# weather_station.net
KiCad netlist of a schematic drawn in EAGLE
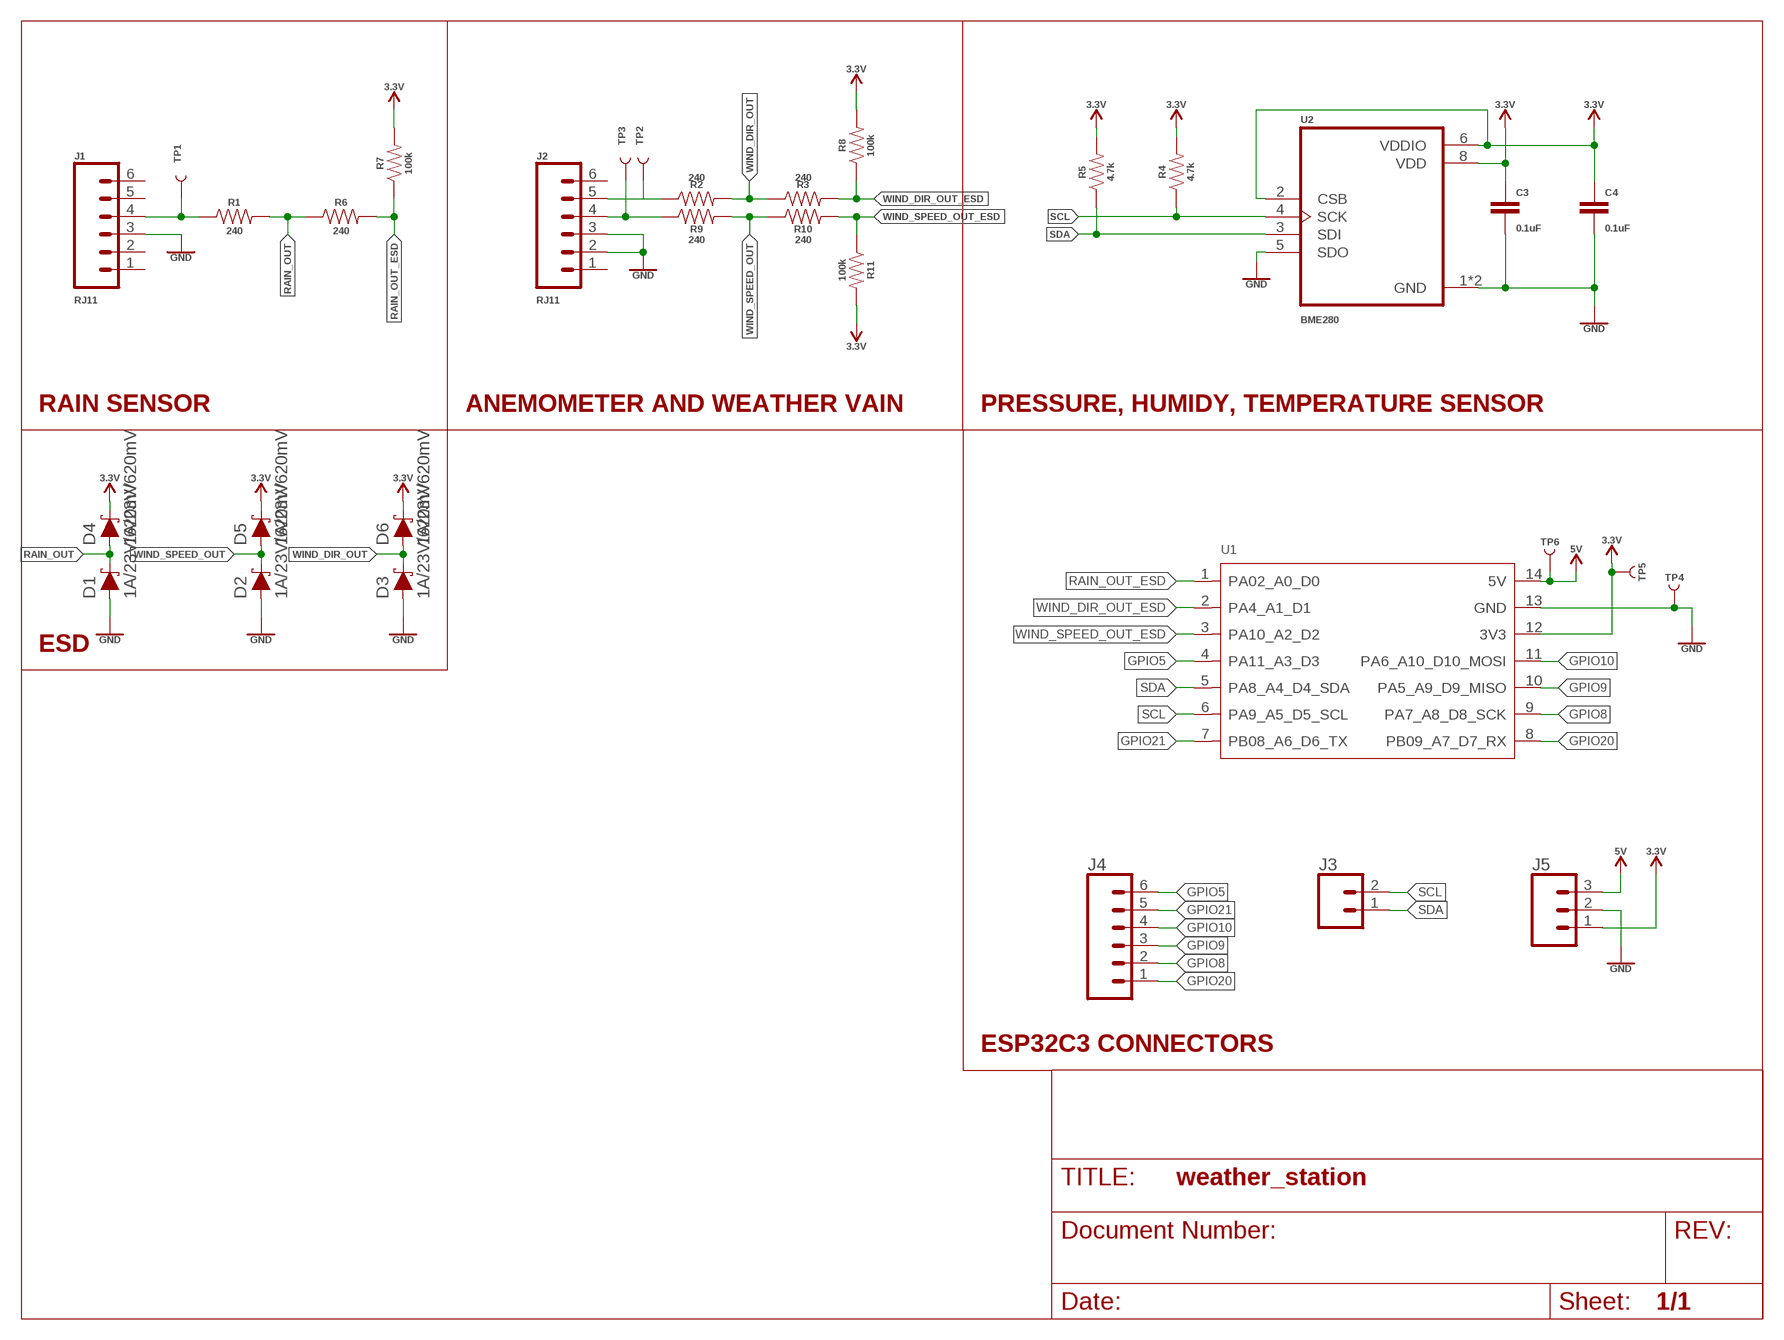
[diagram p0: schematic, sheet 1]

(export (version "E")
  (design (tool "Eeschema 10.0.6"))
  (components
    (comp (ref "C3")
      (value "0.1uF")
      (footprint "eagle-import:0603")
      (libsource (lib "eagle-import") (part "0.1UF-0603-25V-(+80/-20%)"))
    )
    (comp (ref "C4")
      (value "0.1uF")
      (footprint "eagle-import:0603")
      (libsource (lib "eagle-import") (part "0.1UF-0603-25V-(+80/-20%)"))
    )
    (comp (ref "D1")
      (value "1A/23V/620mV")
      (footprint "eagle-import:SOD-323")
      (libsource (lib "eagle-import") (part "DIODE-SCHOTTKY-BAT20J"))
    )
    (comp (ref "D2")
      (value "1A/23V/620mV")
      (footprint "eagle-import:SOD-323")
      (libsource (lib "eagle-import") (part "DIODE-SCHOTTKY-BAT20J"))
    )
    (comp (ref "D3")
      (value "1A/23V/620mV")
      (footprint "eagle-import:SOD-323")
      (libsource (lib "eagle-import") (part "DIODE-SCHOTTKY-BAT20J"))
    )
    (comp (ref "D4")
      (value "1A/23V/620mV")
      (footprint "eagle-import:SOD-323")
      (libsource (lib "eagle-import") (part "DIODE-SCHOTTKY-BAT20J"))
    )
    (comp (ref "D5")
      (value "1A/23V/620mV")
      (footprint "eagle-import:SOD-323")
      (libsource (lib "eagle-import") (part "DIODE-SCHOTTKY-BAT20J"))
    )
    (comp (ref "D6")
      (value "1A/23V/620mV")
      (footprint "eagle-import:SOD-323")
      (libsource (lib "eagle-import") (part "DIODE-SCHOTTKY-BAT20J"))
    )
    (comp (ref "J1")
      (value "RJ11")
      (footprint "eagle-import:RJ11-6")
      (libsource (lib "eagle-import") (part "RJ11-6"))
    )
    (comp (ref "J2")
      (value "RJ11")
      (footprint "eagle-import:RJ11-6")
      (libsource (lib "eagle-import") (part "RJ11-6"))
    )
    (comp (ref "J3")
      (value "CONN_02")
      (footprint "eagle-import:1X02")
      (libsource (lib "eagle-import") (part "CONN_02"))
    )
    (comp (ref "J4")
      (value "CONN_06SILK_FEMALE_PTH")
      (footprint "eagle-import:1X06")
      (libsource (lib "eagle-import") (part "CONN_06SILK_FEMALE_PTH"))
    )
    (comp (ref "J5")
      (value "CONN_03")
      (footprint "eagle-import:1X03")
      (libsource (lib "eagle-import") (part "CONN_03"))
    )
    (comp (ref "R1")
      (value "240")
      (footprint "eagle-import:0603")
      (libsource (lib "eagle-import") (part "240OHM-0603-1/10W-1%"))
    )
    (comp (ref "R2")
      (value "240")
      (footprint "eagle-import:0603")
      (libsource (lib "eagle-import") (part "240OHM-0603-1/10W-1%"))
    )
    (comp (ref "R3")
      (value "240")
      (footprint "eagle-import:0603")
      (libsource (lib "eagle-import") (part "240OHM-0603-1/10W-1%"))
    )
    (comp (ref "R4")
      (value "4.7k")
      (footprint "eagle-import:0603")
      (libsource (lib "eagle-import") (part "4.7KOHM-0603-1/10W-1%"))
    )
    (comp (ref "R5")
      (value "4.7k")
      (footprint "eagle-import:0603")
      (libsource (lib "eagle-import") (part "4.7KOHM-0603-1/10W-1%"))
    )
    (comp (ref "R6")
      (value "240")
      (footprint "eagle-import:0603")
      (libsource (lib "eagle-import") (part "240OHM-0603-1/10W-1%"))
    )
    (comp (ref "R7")
      (value "100k")
      (footprint "eagle-import:0603")
      (libsource (lib "eagle-import") (part "100KOHM-0603-1/10W-1%"))
    )
    (comp (ref "R8")
      (value "100k")
      (footprint "eagle-import:0603")
      (libsource (lib "eagle-import") (part "100KOHM-0603-1/10W-1%"))
    )
    (comp (ref "R9")
      (value "240")
      (footprint "eagle-import:0603")
      (libsource (lib "eagle-import") (part "240OHM-0603-1/10W-1%"))
    )
    (comp (ref "R10")
      (value "240")
      (footprint "eagle-import:0603")
      (libsource (lib "eagle-import") (part "240OHM-0603-1/10W-1%"))
    )
    (comp (ref "R11")
      (value "100k")
      (footprint "eagle-import:0603")
      (libsource (lib "eagle-import") (part "100KOHM-0603-1/10W-1%"))
    )
    (comp (ref "TP1")
      (value "TEST-POINT3")
      (footprint "eagle-import:PAD.03X.03")
      (libsource (lib "eagle-import") (part "TEST-POINT3"))
    )
    (comp (ref "TP2")
      (value "TEST-POINT3")
      (footprint "eagle-import:PAD.03X.03")
      (libsource (lib "eagle-import") (part "TEST-POINT3"))
    )
    (comp (ref "TP3")
      (value "TEST-POINT3")
      (footprint "eagle-import:PAD.03X.03")
      (libsource (lib "eagle-import") (part "TEST-POINT3"))
    )
    (comp (ref "TP4")
      (value "TEST-POINT3")
      (footprint "eagle-import:PAD.03X.03")
      (libsource (lib "eagle-import") (part "TEST-POINT3"))
    )
    (comp (ref "TP5")
      (value "TEST-POINT3")
      (footprint "eagle-import:PAD.03X.03")
      (libsource (lib "eagle-import") (part "TEST-POINT3"))
    )
    (comp (ref "TP6")
      (value "TEST-POINT3")
      (footprint "eagle-import:PAD.03X.03")
      (libsource (lib "eagle-import") (part "TEST-POINT3"))
    )
    (comp (ref "U1")
      (value "MODULE-SEEEDUINO-XIAO-ESP32C3-PIN")
      (footprint "eagle-import:MODULE14P-2.54-21X17.8MM")
      (libsource (lib "eagle-import") (part "MODULE-SEEEDUINO-XIAO-ESP32C3-PIN"))
    )
    (comp (ref "U2")
      (value "BME280")
      (footprint "eagle-import:PSON65P250X250X100-8N")
      (fields (field (name "DIGI-KEY_PART_NUMBER") "828-1063-2-ND") (field (name "MF") "Bosch"))
      (libsource (lib "eagle-import") (part "BME280"))
    )
  )
  (nets
    (net (code "1") (name "3.3V") (class "Default")
      (node (ref "C3") (pin "1") (pinfunction "1_1") (pintype "passive"))
      (node (ref "C4") (pin "1") (pinfunction "1_1") (pintype "passive"))
      (node (ref "D4") (pin "C") (pinfunction "C_C") (pintype "passive"))
      (node (ref "D5") (pin "C") (pinfunction "C_C") (pintype "passive"))
      (node (ref "D6") (pin "C") (pinfunction "C_C") (pintype "passive"))
      (node (ref "J5") (pin "1") (pinfunction "1_1") (pintype "passive"))
      (node (ref "R11") (pin "2") (pinfunction "2_2") (pintype "passive"))
      (node (ref "R4") (pin "2") (pinfunction "2_2") (pintype "passive"))
      (node (ref "R5") (pin "2") (pinfunction "2_2") (pintype "passive"))
      (node (ref "R7") (pin "2") (pinfunction "2_2") (pintype "passive"))
      (node (ref "R8") (pin "2") (pinfunction "2_2") (pintype "passive"))
      (node (ref "TP5") (pin "P$1") (pinfunction "1_P$1") (pintype "bidirectional"))
      (node (ref "U1") (pin "12") (pinfunction "3V3_12") (pintype "bidirectional"))
      (node (ref "U2") (pin "2") (pinfunction "CSB_2") (pintype "input"))
      (node (ref "U2") (pin "6") (pinfunction "VDDIO_6") (pintype "power_in"))
      (node (ref "U2") (pin "8") (pinfunction "VDD_8") (pintype "power_in"))
    )
    (net (code "2") (name "5V") (class "Default")
      (node (ref "J5") (pin "3") (pinfunction "3_3") (pintype "passive"))
      (node (ref "TP6") (pin "P$1") (pinfunction "1_P$1") (pintype "bidirectional"))
      (node (ref "U1") (pin "14") (pinfunction "5V_14") (pintype "bidirectional"))
    )
    (net (code "3") (name "GND") (class "Default")
      (node (ref "C3") (pin "2") (pinfunction "2_2") (pintype "passive"))
      (node (ref "C4") (pin "2") (pinfunction "2_2") (pintype "passive"))
      (node (ref "D1") (pin "A") (pinfunction "A_A") (pintype "passive"))
      (node (ref "D2") (pin "A") (pinfunction "A_A") (pintype "passive"))
      (node (ref "D3") (pin "A") (pinfunction "A_A") (pintype "passive"))
      (node (ref "J1") (pin "3") (pinfunction "3_3") (pintype "passive"))
      (node (ref "J2") (pin "2") (pinfunction "2_2") (pintype "passive"))
      (node (ref "J2") (pin "3") (pinfunction "3_3") (pintype "passive"))
      (node (ref "J5") (pin "2") (pinfunction "2_2") (pintype "passive"))
      (node (ref "TP4") (pin "P$1") (pinfunction "1_P$1") (pintype "bidirectional"))
      (node (ref "U1") (pin "13") (pinfunction "GND_13") (pintype "bidirectional"))
      (node (ref "U2") (pin "1") (pinfunction "GND_1") (pintype "power_in"))
      (node (ref "U2") (pin "5") (pinfunction "SDO_5") (pintype "bidirectional"))
      (node (ref "U2") (pin "7") (pinfunction "GND_7") (pintype "power_in"))
    )
    (net (code "4") (name "GPIO5") (class "Default")
      (node (ref "J4") (pin "6") (pinfunction "6_6") (pintype "passive"))
      (node (ref "U1") (pin "4") (pinfunction "PA11_A3_D3_4") (pintype "bidirectional"))
    )
    (net (code "5") (name "GPIO8") (class "Default")
      (node (ref "J4") (pin "2") (pinfunction "2_2") (pintype "passive"))
      (node (ref "U1") (pin "9") (pinfunction "PA7_A8_D8_SCK_9") (pintype "bidirectional"))
    )
    (net (code "6") (name "GPIO9") (class "Default")
      (node (ref "J4") (pin "3") (pinfunction "3_3") (pintype "passive"))
      (node (ref "U1") (pin "10") (pinfunction "PA5_A9_D9_MISO_10") (pintype "bidirectional"))
    )
    (net (code "7") (name "GPIO10") (class "Default")
      (node (ref "J4") (pin "4") (pinfunction "4_4") (pintype "passive"))
      (node (ref "U1") (pin "11") (pinfunction "PA6_A10_D10_MOSI_11") (pintype "bidirectional"))
    )
    (net (code "8") (name "GPIO20") (class "Default")
      (node (ref "J4") (pin "1") (pinfunction "1_1") (pintype "passive"))
      (node (ref "U1") (pin "8") (pinfunction "PB09_A7_D7_RX_8") (pintype "bidirectional"))
    )
    (net (code "9") (name "GPIO21") (class "Default")
      (node (ref "J4") (pin "5") (pinfunction "5_5") (pintype "passive"))
      (node (ref "U1") (pin "7") (pinfunction "PB08_A6_D6_TX_7") (pintype "bidirectional"))
    )
    (net (code "10") (name "Net-(TP1-1)") (class "Default")
      (node (ref "J1") (pin "4") (pinfunction "4_4") (pintype "passive"))
      (node (ref "R1") (pin "1") (pinfunction "1_1") (pintype "passive"))
      (node (ref "TP1") (pin "P$1") (pinfunction "1_P$1") (pintype "bidirectional"))
    )
    (net (code "11") (name "Net-(TP2-1)") (class "Default")
      (node (ref "J2") (pin "5") (pinfunction "5_5") (pintype "passive"))
      (node (ref "R2") (pin "1") (pinfunction "1_1") (pintype "passive"))
      (node (ref "TP2") (pin "P$1") (pinfunction "1_P$1") (pintype "bidirectional"))
    )
    (net (code "12") (name "Net-(TP3-1)") (class "Default")
      (node (ref "J2") (pin "4") (pinfunction "4_4") (pintype "passive"))
      (node (ref "R9") (pin "1") (pinfunction "1_1") (pintype "passive"))
      (node (ref "TP3") (pin "P$1") (pinfunction "1_P$1") (pintype "bidirectional"))
    )
    (net (code "13") (name "RAIN_OUT") (class "Default")
      (node (ref "D1") (pin "C") (pinfunction "C_C") (pintype "passive"))
      (node (ref "D4") (pin "A") (pinfunction "A_A") (pintype "passive"))
      (node (ref "R1") (pin "2") (pinfunction "2_2") (pintype "passive"))
      (node (ref "R6") (pin "1") (pinfunction "1_1") (pintype "passive"))
    )
    (net (code "14") (name "RAIN_OUT_ESD") (class "Default")
      (node (ref "R6") (pin "2") (pinfunction "2_2") (pintype "passive"))
      (node (ref "R7") (pin "1") (pinfunction "1_1") (pintype "passive"))
      (node (ref "U1") (pin "1") (pinfunction "PA02_A0_D0_1") (pintype "bidirectional"))
    )
    (net (code "15") (name "SCL") (class "Default")
      (node (ref "J3") (pin "2") (pinfunction "2_2") (pintype "passive"))
      (node (ref "R4") (pin "1") (pinfunction "1_1") (pintype "passive"))
      (node (ref "U1") (pin "6") (pinfunction "PA9_A5_D5_SCL_6") (pintype "bidirectional"))
      (node (ref "U2") (pin "4") (pinfunction "SCK_4") (pintype "input"))
    )
    (net (code "16") (name "SDA") (class "Default")
      (node (ref "J3") (pin "1") (pinfunction "1_1") (pintype "passive"))
      (node (ref "R5") (pin "1") (pinfunction "1_1") (pintype "passive"))
      (node (ref "U1") (pin "5") (pinfunction "PA8_A4_D4_SDA_5") (pintype "bidirectional"))
      (node (ref "U2") (pin "3") (pinfunction "SDI_3") (pintype "bidirectional"))
    )
    (net (code "17") (name "WIND_DIR_OUT") (class "Default")
      (node (ref "D3") (pin "C") (pinfunction "C_C") (pintype "passive"))
      (node (ref "D6") (pin "A") (pinfunction "A_A") (pintype "passive"))
      (node (ref "R2") (pin "2") (pinfunction "2_2") (pintype "passive"))
      (node (ref "R3") (pin "1") (pinfunction "1_1") (pintype "passive"))
    )
    (net (code "18") (name "WIND_DIR_OUT_ESD") (class "Default")
      (node (ref "R3") (pin "2") (pinfunction "2_2") (pintype "passive"))
      (node (ref "R8") (pin "1") (pinfunction "1_1") (pintype "passive"))
      (node (ref "U1") (pin "2") (pinfunction "PA4_A1_D1_2") (pintype "bidirectional"))
    )
    (net (code "19") (name "WIND_SPEED_OUT") (class "Default")
      (node (ref "D2") (pin "C") (pinfunction "C_C") (pintype "passive"))
      (node (ref "D5") (pin "A") (pinfunction "A_A") (pintype "passive"))
      (node (ref "R10") (pin "1") (pinfunction "1_1") (pintype "passive"))
      (node (ref "R9") (pin "2") (pinfunction "2_2") (pintype "passive"))
    )
    (net (code "20") (name "WIND_SPEED_OUT_ESD") (class "Default")
      (node (ref "R10") (pin "2") (pinfunction "2_2") (pintype "passive"))
      (node (ref "R11") (pin "1") (pinfunction "1_1") (pintype "passive"))
      (node (ref "U1") (pin "3") (pinfunction "PA10_A2_D2_3") (pintype "bidirectional"))
    )
    (net (code "21") (name "unconnected-(J1-Pad1)") (class "Default")
      (node (ref "J1") (pin "1") (pinfunction "1_1") (pintype "passive"))
    )
    (net (code "22") (name "unconnected-(J1-Pad2)") (class "Default")
      (node (ref "J1") (pin "2") (pinfunction "2_2") (pintype "passive"))
    )
    (net (code "23") (name "unconnected-(J1-Pad5)") (class "Default")
      (node (ref "J1") (pin "5") (pinfunction "5_5") (pintype "passive"))
    )
    (net (code "24") (name "unconnected-(J1-Pad6)") (class "Default")
      (node (ref "J1") (pin "6") (pinfunction "6_6") (pintype "passive"))
    )
    (net (code "25") (name "unconnected-(J2-Pad1)") (class "Default")
      (node (ref "J2") (pin "1") (pinfunction "1_1") (pintype "passive"))
    )
    (net (code "26") (name "unconnected-(J2-Pad6)") (class "Default")
      (node (ref "J2") (pin "6") (pinfunction "6_6") (pintype "passive"))
    )
  )
)
